# IOT_D1-Mini-1_v3.net
KiCad netlist of a schematic drawn in EAGLE
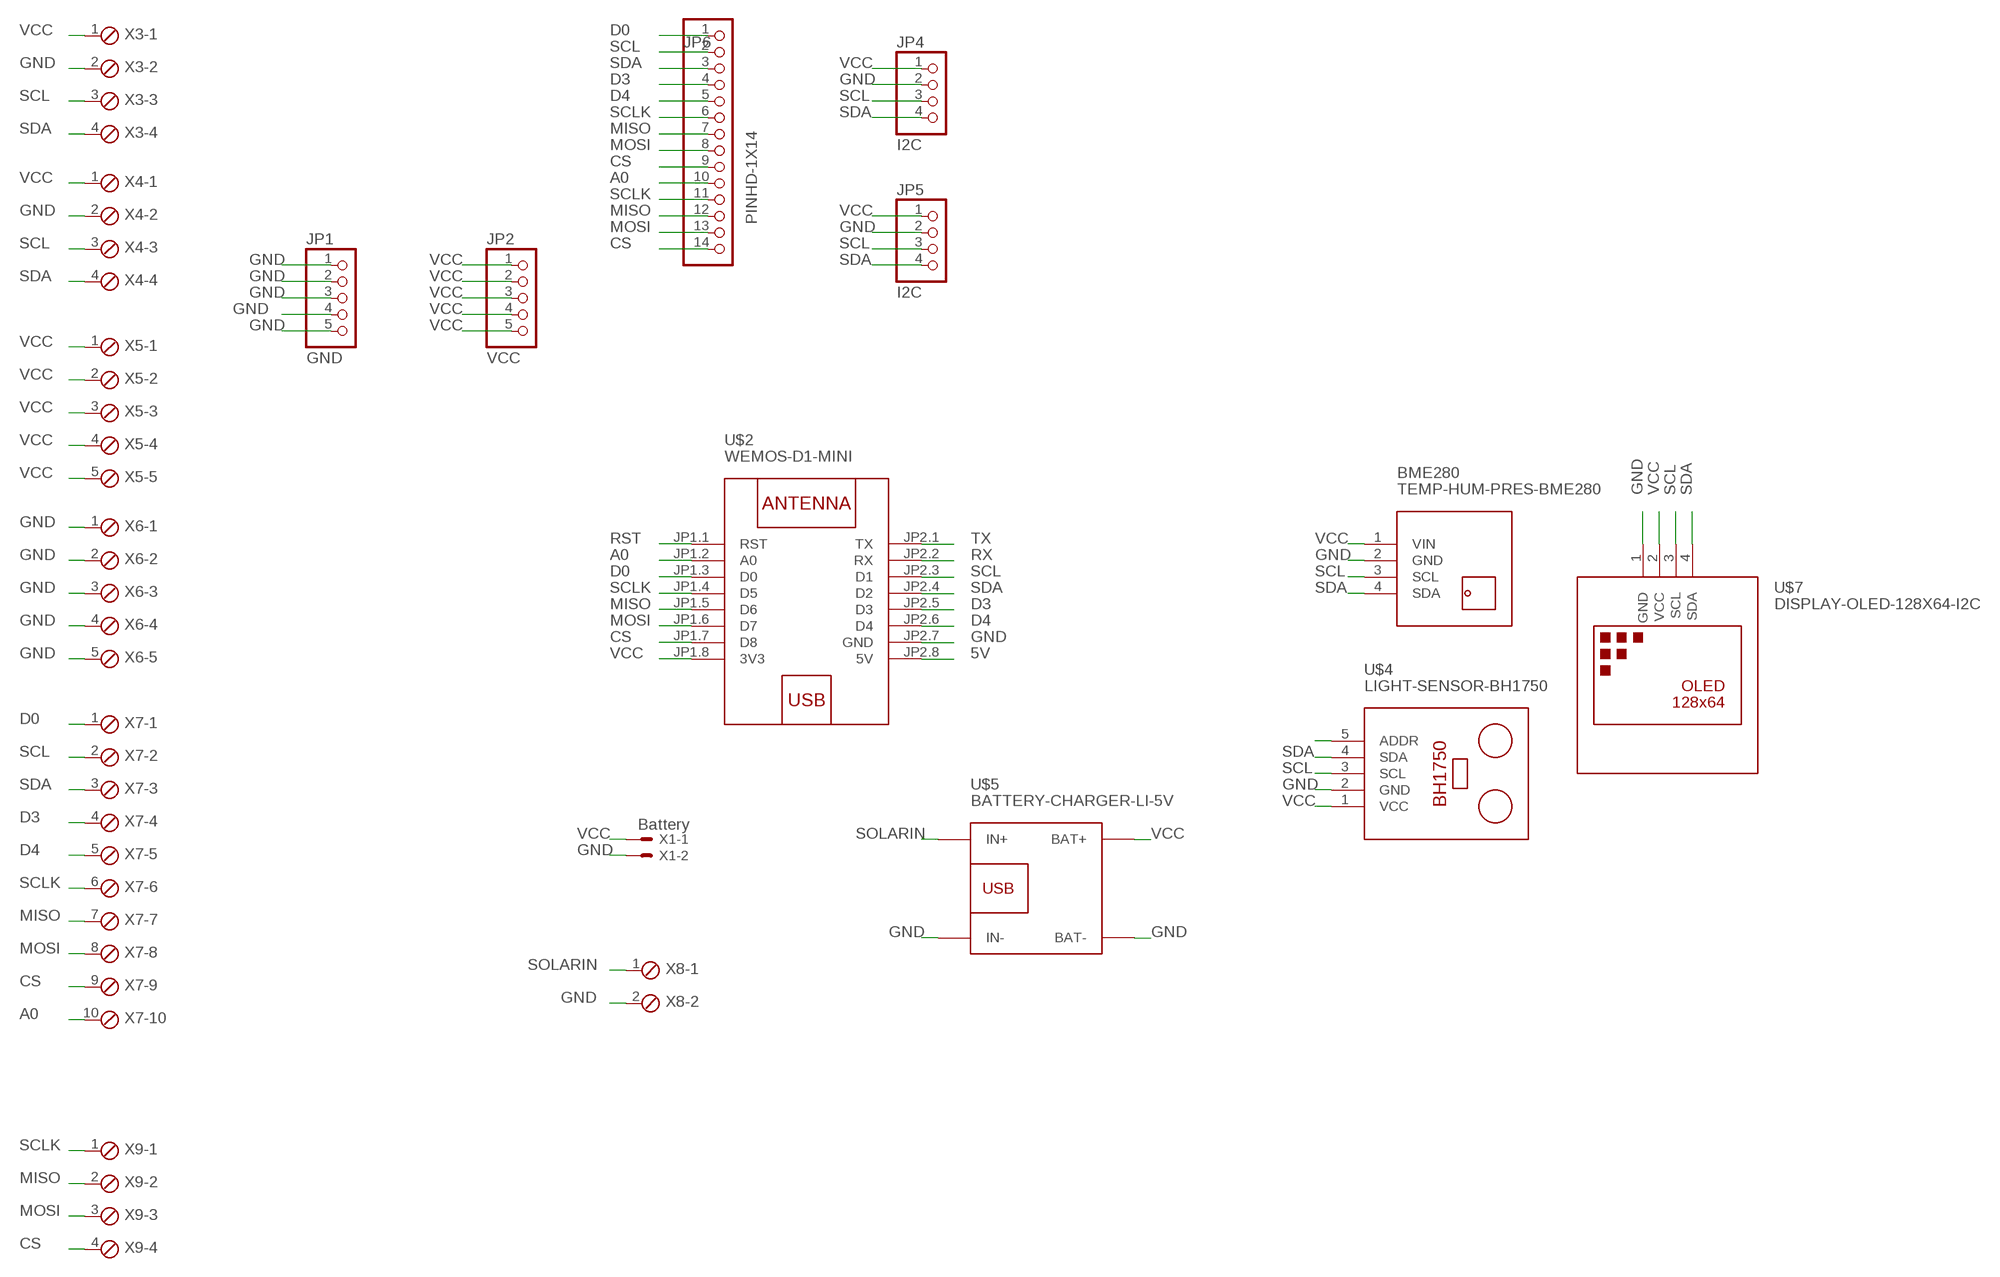
[diagram p0: schematic, sheet 1]

(export (version "E")
  (design (tool "Eeschema 10.0.6"))
  (components
    (comp (ref "BME280")
      (value "TEMP-HUM-PRES-BME280")
      (footprint "eagle-import:TEMP-HUM-PRES-BME280")
      (libsource (lib "eagle-import") (part "TEMP-HUM-PRES-BME280"))
    )
    (comp (ref "JP1")
      (value "GND")
      (footprint "eagle-import:1X05")
      (libsource (lib "eagle-import") (part "PINHD-1X5"))
    )
    (comp (ref "JP2")
      (value "VCC")
      (footprint "eagle-import:1X05")
      (libsource (lib "eagle-import") (part "PINHD-1X5"))
    )
    (comp (ref "JP4")
      (value "I2C")
      (footprint "eagle-import:1X04")
      (libsource (lib "eagle-import") (part "PINHD-1X4"))
    )
    (comp (ref "JP5")
      (value "I2C")
      (footprint "eagle-import:1X04")
      (libsource (lib "eagle-import") (part "PINHD-1X4"))
    )
    (comp (ref "JP6")
      (value "PINHD-1X14")
      (footprint "eagle-import:1X14")
      (libsource (lib "eagle-import") (part "PINHD-1X14"))
    )
    (comp (ref "U$2")
      (value "WEMOS-D1-MINI")
      (footprint "eagle-import:WEMOS-D1-MINI")
      (libsource (lib "eagle-import") (part "WEMOS-D1-MINI"))
    )
    (comp (ref "U$4")
      (value "LIGHT-SENSOR-BH1750")
      (footprint "eagle-import:LIGHT-SENSOR-BH1750")
      (libsource (lib "eagle-import") (part "LIGHT-SENSOR-BH1750"))
    )
    (comp (ref "U$5")
      (value "BATTERY-CHARGER-LI-5V")
      (footprint "eagle-import:BATTERY-CHARGER-LI-5V")
      (libsource (lib "eagle-import") (part "BATTERY-CHARGER-LI-5V"))
    )
    (comp (ref "U$7")
      (value "DISPLAY-OLED-128X64-I2C")
      (footprint "eagle-import:DISPLAY-OLED-128X64-I2C")
      (libsource (lib "eagle-import") (part "DISPLAY-OLED-128X64-I2C"))
    )
    (comp (ref "X1")
      (value "Battery")
      (footprint "eagle-import:53047-02")
      (fields (field (name "MF") "MOLEX") (field (name "MPN") "53047-0210"))
      (libsource (lib "eagle-import") (part "53?-02047"))
    )
    (comp (ref "X3")
      (value "MPT4")
      (footprint "eagle-import:4POL254")
      (libsource (lib "eagle-import") (part "MPT4"))
    )
    (comp (ref "X4")
      (value "MPT4")
      (footprint "eagle-import:4POL254")
      (libsource (lib "eagle-import") (part "MPT4"))
    )
    (comp (ref "X5")
      (value "MPT5")
      (footprint "eagle-import:5POL254")
      (libsource (lib "eagle-import") (part "MPT5"))
    )
    (comp (ref "X6")
      (value "MPT5")
      (footprint "eagle-import:5POL254")
      (libsource (lib "eagle-import") (part "MPT5"))
    )
    (comp (ref "X7")
      (value "MPT10")
      (footprint "eagle-import:10POL254")
      (libsource (lib "eagle-import") (part "MPT10"))
    )
    (comp (ref "X8")
      (value "MPT2")
      (footprint "eagle-import:2POL254")
      (libsource (lib "eagle-import") (part "MPT2"))
    )
    (comp (ref "X9")
      (value "MPT4")
      (footprint "eagle-import:4POL254")
      (libsource (lib "eagle-import") (part "MPT4"))
    )
  )
  (nets
    (net (code "1") (name "/5V") (class "Default")
      (node (ref "U$2") (pin "JP2.8") (pinfunction "5V_JP2.8") (pintype "power_in"))
    )
    (net (code "2") (name "/A0") (class "Default")
      (node (ref "JP6") (pin "10") (pinfunction "10_10") (pintype "passive"))
      (node (ref "U$2") (pin "JP1.2") (pinfunction "A0_JP1.2") (pintype "bidirectional"))
      (node (ref "X7") (pin "10") (pinfunction "1_10") (pintype "passive"))
    )
    (net (code "3") (name "/CS") (class "Default")
      (node (ref "JP6") (pin "14") (pinfunction "14_14") (pintype "passive"))
      (node (ref "JP6") (pin "9") (pinfunction "9_9") (pintype "passive"))
      (node (ref "U$2") (pin "JP1.7") (pinfunction "D8_JP1.7") (pintype "bidirectional"))
      (node (ref "X7") (pin "9") (pinfunction "1_9") (pintype "passive"))
      (node (ref "X9") (pin "4") (pinfunction "1_4") (pintype "passive"))
    )
    (net (code "4") (name "/D0") (class "Default")
      (node (ref "JP6") (pin "1") (pinfunction "1_1") (pintype "passive"))
      (node (ref "U$2") (pin "JP1.3") (pinfunction "D0_JP1.3") (pintype "bidirectional"))
      (node (ref "X7") (pin "1") (pinfunction "1_1") (pintype "passive"))
    )
    (net (code "5") (name "/D3") (class "Default")
      (node (ref "JP6") (pin "4") (pinfunction "4_4") (pintype "passive"))
      (node (ref "U$2") (pin "JP2.5") (pinfunction "D3_JP2.5") (pintype "bidirectional"))
      (node (ref "X7") (pin "4") (pinfunction "1_4") (pintype "passive"))
    )
    (net (code "6") (name "/D4") (class "Default")
      (node (ref "JP6") (pin "5") (pinfunction "5_5") (pintype "passive"))
      (node (ref "U$2") (pin "JP2.6") (pinfunction "D4_JP2.6") (pintype "bidirectional"))
      (node (ref "X7") (pin "5") (pinfunction "1_5") (pintype "passive"))
    )
    (net (code "7") (name "/GND") (class "Default")
      (node (ref "BME280") (pin "2") (pinfunction "GND_2") (pintype "power_in"))
      (node (ref "JP1") (pin "1") (pinfunction "1_1") (pintype "passive"))
      (node (ref "JP1") (pin "2") (pinfunction "2_2") (pintype "passive"))
      (node (ref "JP1") (pin "3") (pinfunction "3_3") (pintype "passive"))
      (node (ref "JP1") (pin "4") (pinfunction "4_4") (pintype "passive"))
      (node (ref "JP1") (pin "5") (pinfunction "5_5") (pintype "passive"))
      (node (ref "JP4") (pin "2") (pinfunction "2_2") (pintype "passive"))
      (node (ref "JP5") (pin "2") (pinfunction "2_2") (pintype "passive"))
      (node (ref "U$2") (pin "JP2.7") (pinfunction "GND_JP2.7") (pintype "power_in"))
      (node (ref "U$4") (pin "2") (pinfunction "GND_2") (pintype "power_in"))
      (node (ref "U$5") (pin "BAT-") (pinfunction "BAT-_BAT-") (pintype "bidirectional"))
      (node (ref "U$5") (pin "IN-") (pinfunction "IN-_IN-") (pintype "bidirectional"))
      (node (ref "U$7") (pin "1") (pinfunction "GND_1") (pintype "power_in"))
      (node (ref "X1") (pin "2") (pinfunction "S_2") (pintype "passive"))
      (node (ref "X3") (pin "2") (pinfunction "1_2") (pintype "passive"))
      (node (ref "X4") (pin "2") (pinfunction "1_2") (pintype "passive"))
      (node (ref "X6") (pin "1") (pinfunction "1_1") (pintype "passive"))
      (node (ref "X6") (pin "2") (pinfunction "1_2") (pintype "passive"))
      (node (ref "X6") (pin "3") (pinfunction "1_3") (pintype "passive"))
      (node (ref "X6") (pin "4") (pinfunction "1_4") (pintype "passive"))
      (node (ref "X6") (pin "5") (pinfunction "1_5") (pintype "passive"))
      (node (ref "X8") (pin "2") (pinfunction "1_2") (pintype "passive"))
    )
    (net (code "8") (name "/MISO") (class "Default")
      (node (ref "JP6") (pin "12") (pinfunction "12_12") (pintype "passive"))
      (node (ref "JP6") (pin "7") (pinfunction "7_7") (pintype "passive"))
      (node (ref "U$2") (pin "JP1.5") (pinfunction "D6_JP1.5") (pintype "bidirectional"))
      (node (ref "X7") (pin "7") (pinfunction "1_7") (pintype "passive"))
      (node (ref "X9") (pin "2") (pinfunction "1_2") (pintype "passive"))
    )
    (net (code "9") (name "/MOSI") (class "Default")
      (node (ref "JP6") (pin "13") (pinfunction "13_13") (pintype "passive"))
      (node (ref "JP6") (pin "8") (pinfunction "8_8") (pintype "passive"))
      (node (ref "U$2") (pin "JP1.6") (pinfunction "D7_JP1.6") (pintype "bidirectional"))
      (node (ref "X7") (pin "8") (pinfunction "1_8") (pintype "passive"))
      (node (ref "X9") (pin "3") (pinfunction "1_3") (pintype "passive"))
    )
    (net (code "10") (name "/RST") (class "Default")
      (node (ref "U$2") (pin "JP1.1") (pinfunction "RST_JP1.1") (pintype "bidirectional"))
    )
    (net (code "11") (name "/RX") (class "Default")
      (node (ref "U$2") (pin "JP2.2") (pinfunction "RX_JP2.2") (pintype "bidirectional"))
    )
    (net (code "12") (name "/SCL") (class "Default")
      (node (ref "BME280") (pin "3") (pinfunction "SCL_3") (pintype "bidirectional"))
      (node (ref "JP4") (pin "3") (pinfunction "3_3") (pintype "passive"))
      (node (ref "JP5") (pin "3") (pinfunction "3_3") (pintype "passive"))
      (node (ref "JP6") (pin "2") (pinfunction "2_2") (pintype "passive"))
      (node (ref "U$2") (pin "JP2.3") (pinfunction "D1_JP2.3") (pintype "bidirectional"))
      (node (ref "U$4") (pin "3") (pinfunction "SCL_3") (pintype "bidirectional"))
      (node (ref "U$7") (pin "3") (pinfunction "SCL_3") (pintype "bidirectional"))
      (node (ref "X3") (pin "3") (pinfunction "1_3") (pintype "passive"))
      (node (ref "X4") (pin "3") (pinfunction "1_3") (pintype "passive"))
      (node (ref "X7") (pin "2") (pinfunction "1_2") (pintype "passive"))
    )
    (net (code "13") (name "/SCLK") (class "Default")
      (node (ref "JP6") (pin "11") (pinfunction "11_11") (pintype "passive"))
      (node (ref "JP6") (pin "6") (pinfunction "6_6") (pintype "passive"))
      (node (ref "U$2") (pin "JP1.4") (pinfunction "D5_JP1.4") (pintype "bidirectional"))
      (node (ref "X7") (pin "6") (pinfunction "1_6") (pintype "passive"))
      (node (ref "X9") (pin "1") (pinfunction "1_1") (pintype "passive"))
    )
    (net (code "14") (name "/SDA") (class "Default")
      (node (ref "BME280") (pin "4") (pinfunction "SDA_4") (pintype "bidirectional"))
      (node (ref "JP4") (pin "4") (pinfunction "4_4") (pintype "passive"))
      (node (ref "JP5") (pin "4") (pinfunction "4_4") (pintype "passive"))
      (node (ref "JP6") (pin "3") (pinfunction "3_3") (pintype "passive"))
      (node (ref "U$2") (pin "JP2.4") (pinfunction "D2_JP2.4") (pintype "bidirectional"))
      (node (ref "U$4") (pin "4") (pinfunction "SDA_4") (pintype "bidirectional"))
      (node (ref "U$7") (pin "4") (pinfunction "SDA_4") (pintype "bidirectional"))
      (node (ref "X3") (pin "4") (pinfunction "1_4") (pintype "passive"))
      (node (ref "X4") (pin "4") (pinfunction "1_4") (pintype "passive"))
      (node (ref "X7") (pin "3") (pinfunction "1_3") (pintype "passive"))
    )
    (net (code "15") (name "/SOLARIN") (class "Default")
      (node (ref "U$5") (pin "IN+") (pinfunction "IN+_IN+") (pintype "bidirectional"))
      (node (ref "X8") (pin "1") (pinfunction "1_1") (pintype "passive"))
    )
    (net (code "16") (name "/TX") (class "Default")
      (node (ref "U$2") (pin "JP2.1") (pinfunction "TX_JP2.1") (pintype "bidirectional"))
    )
    (net (code "17") (name "/VCC") (class "Default")
      (node (ref "BME280") (pin "1") (pinfunction "VIN_1") (pintype "power_in"))
      (node (ref "JP2") (pin "1") (pinfunction "1_1") (pintype "passive"))
      (node (ref "JP2") (pin "2") (pinfunction "2_2") (pintype "passive"))
      (node (ref "JP2") (pin "3") (pinfunction "3_3") (pintype "passive"))
      (node (ref "JP2") (pin "4") (pinfunction "4_4") (pintype "passive"))
      (node (ref "JP2") (pin "5") (pinfunction "5_5") (pintype "passive"))
      (node (ref "JP4") (pin "1") (pinfunction "1_1") (pintype "passive"))
      (node (ref "JP5") (pin "1") (pinfunction "1_1") (pintype "passive"))
      (node (ref "U$2") (pin "JP1.8") (pinfunction "3V3_JP1.8") (pintype "power_in"))
      (node (ref "U$4") (pin "1") (pinfunction "VCC_1") (pintype "power_in"))
      (node (ref "U$5") (pin "BAT+") (pinfunction "BAT+_BAT+") (pintype "bidirectional"))
      (node (ref "U$7") (pin "2") (pinfunction "VCC_2") (pintype "power_in"))
      (node (ref "X1") (pin "1") (pinfunction "S_1") (pintype "passive"))
      (node (ref "X3") (pin "1") (pinfunction "1_1") (pintype "passive"))
      (node (ref "X4") (pin "1") (pinfunction "1_1") (pintype "passive"))
      (node (ref "X5") (pin "1") (pinfunction "1_1") (pintype "passive"))
      (node (ref "X5") (pin "2") (pinfunction "1_2") (pintype "passive"))
      (node (ref "X5") (pin "3") (pinfunction "1_3") (pintype "passive"))
      (node (ref "X5") (pin "4") (pinfunction "1_4") (pintype "passive"))
      (node (ref "X5") (pin "5") (pinfunction "1_5") (pintype "passive"))
    )
    (net (code "18") (name "unconnected-(U$4-ADDR-Pad5)") (class "Default")
      (node (ref "U$4") (pin "5") (pinfunction "ADDR_5") (pintype "bidirectional"))
    )
  )
)
